# MCU099_01_MSPM0L1306_Target_Device.net
KiCad netlist of a schematic drawn in Altium Designer
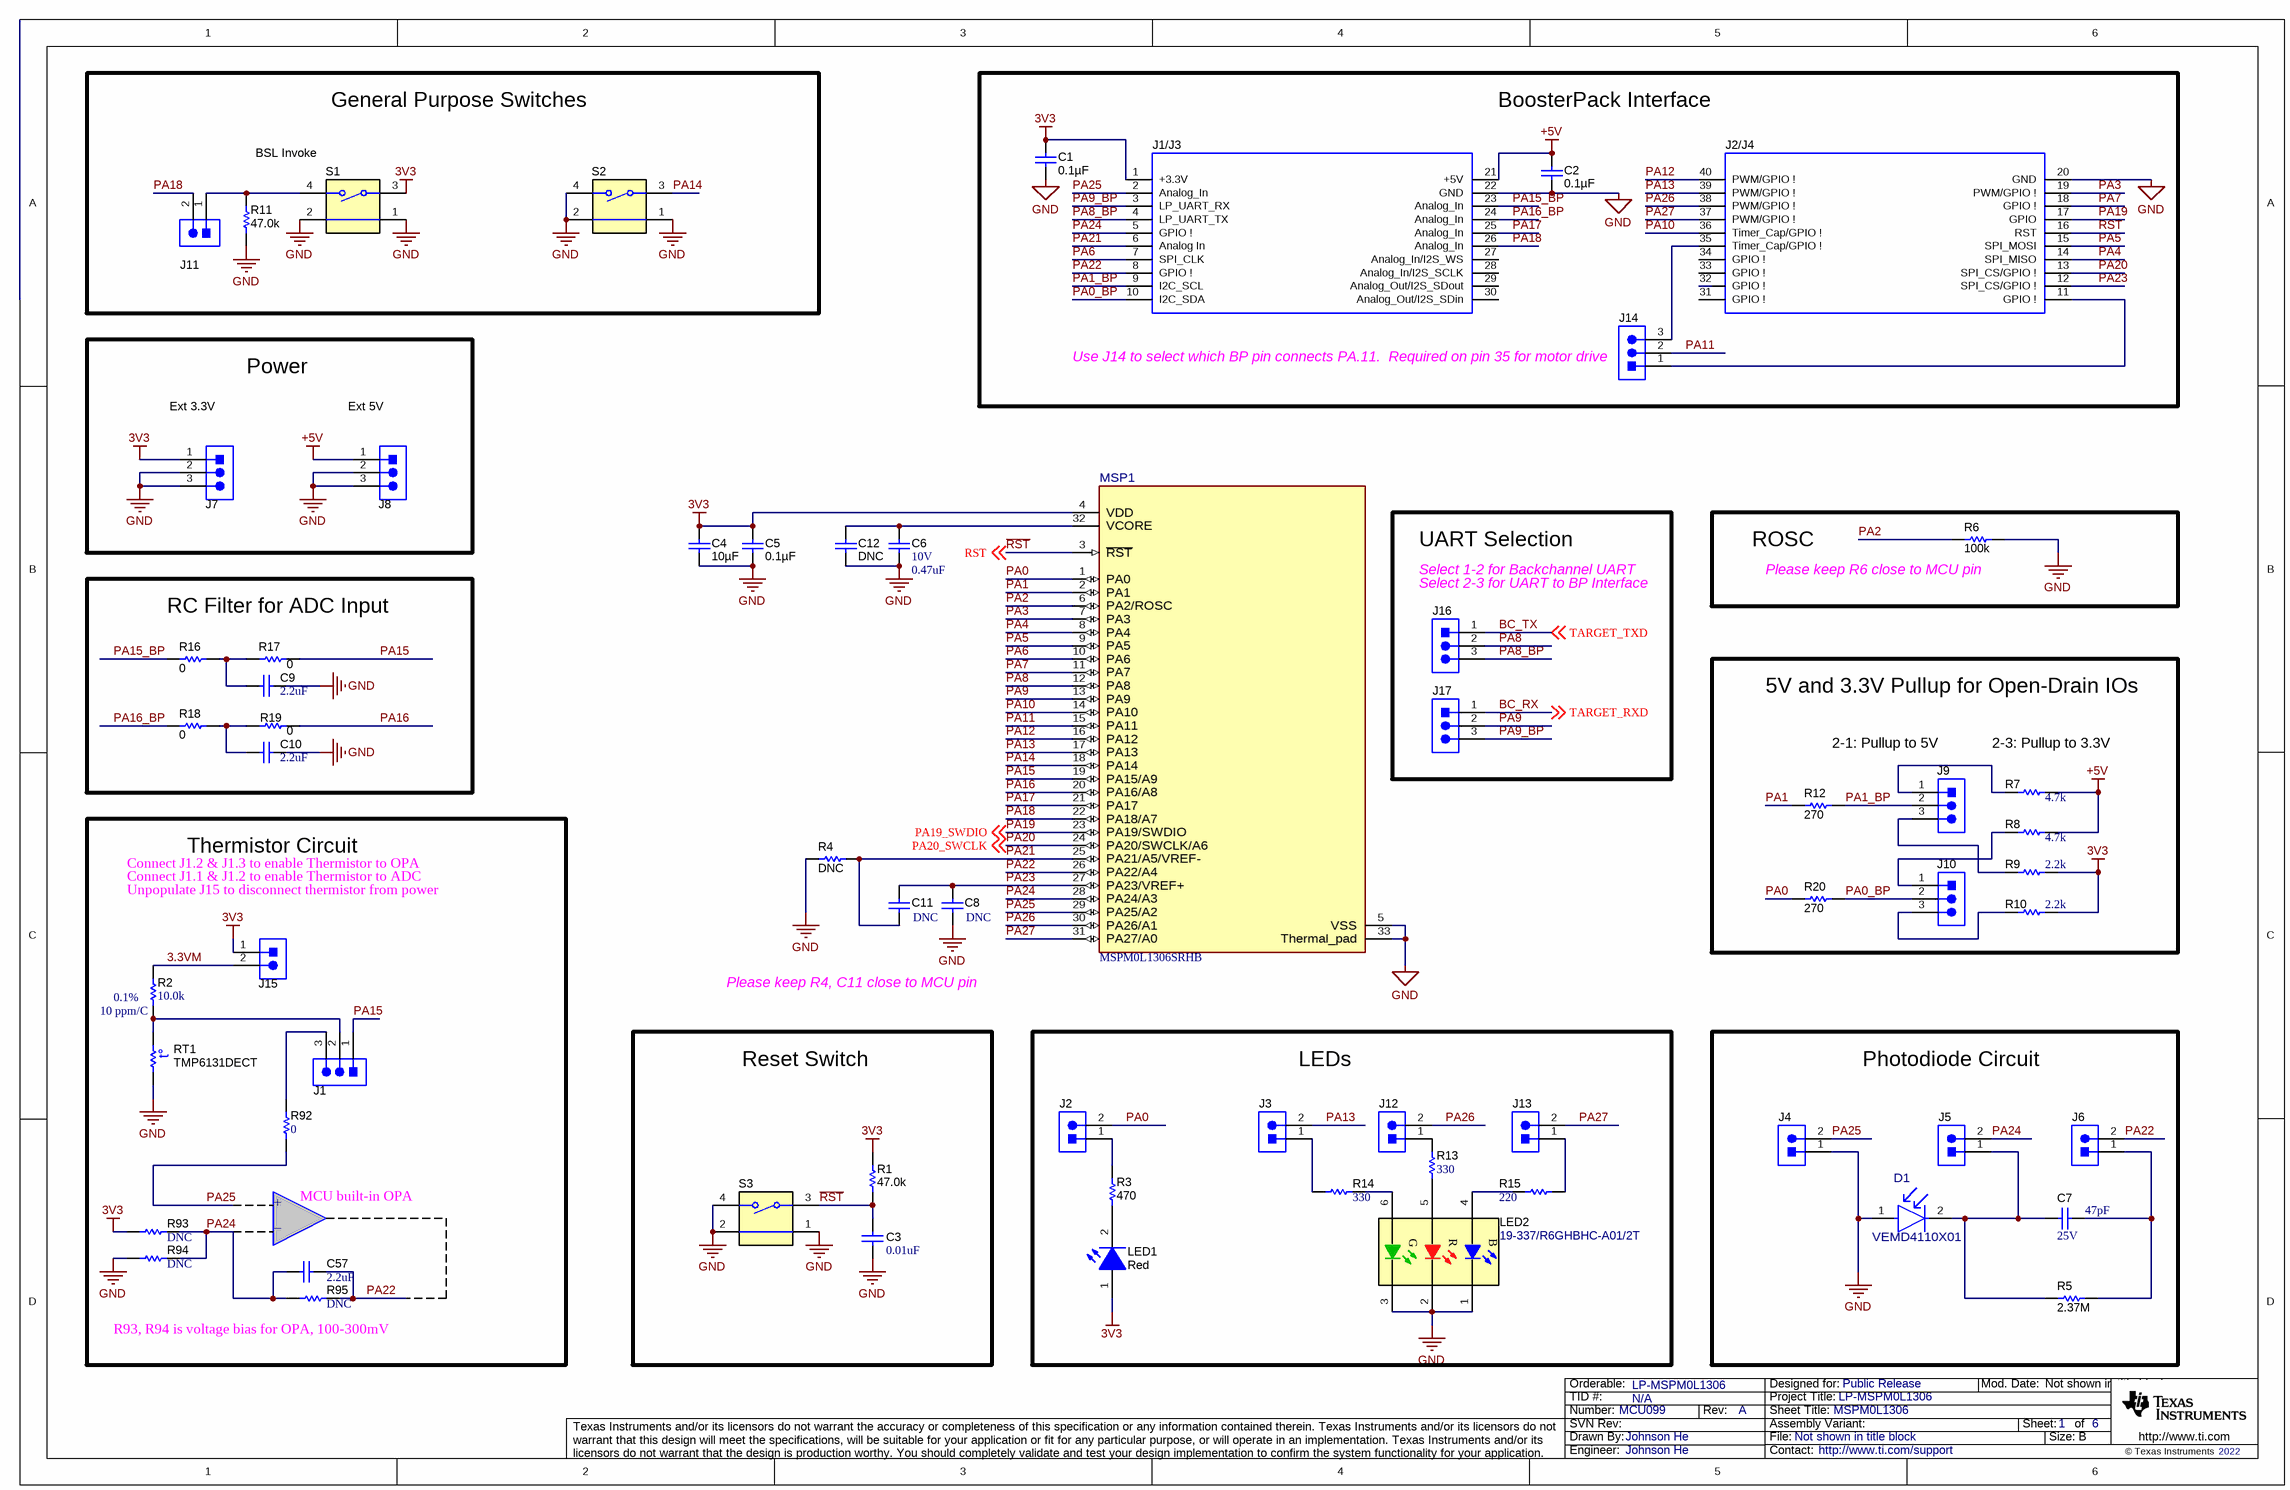
[diagram p0: MCU099_01_MSPM0L1306_Target_Device.SchDoc]

(export (version "E")
  (design (tool "Eeschema 10.0.6"))
  (components
    (comp (ref "C1")
      (value "CL10A104KA8NNNC")
      (footprint "0603")
      (description "CAP, CERM, 0.1 µF, 25 V,+/- 10%, X5R, 0603")
      (fields
        (field (name "VALUEDISPLAYED") "0.1µF")
        (field (name "MANUFACTURER") "Samsung Electro-Mechanics")
      )
      (libsource (lib "Altium Vault - TI") (part "Capacitor"))
    )
    (comp (ref "C2")
      (value "CL10A104KA8NNNC")
      (footprint "0603")
      (description "CAP, CERM, 0.1 µF, 25 V,+/- 10%, X5R, 0603")
      (fields
        (field (name "VALUEDISPLAYED") "0.1µF")
        (field (name "MANUFACTURER") "Samsung Electro-Mechanics")
      )
      (libsource (lib "Altium Vault - TI") (part "Capacitor"))
    )
    (comp (ref "C3")
      (value "885012205031")
      (footprint "0402")
      (description "CAP, CERM, 0.01 uF, 16 V, +/- 10%, X7R, 0402")
      (fields
        (field (name "MANUFACTURER") "Wurth Elektronik")
        (field (name "VALUEDISPLAYED") "0.01uF")
        (field (name "PUBLISHER") "Texas Instruments")
      )
      (libsource (lib "Altium Vault - TI") (part "Capacitor"))
    )
    (comp (ref "C4")
      (value "GRM188R61C106KAALD")
      (footprint "0603")
      (description "CAP, CERM, 10 µF, 16 V,+/- 10%, X5R, 0603")
      (fields (field (name "MANUFACTURER") "MuRata") (field (name "VALUEDISPLAYED") "10µF"))
      (libsource (lib "Altium Vault - TI") (part "Capacitor"))
    )
    (comp (ref "C5")
      (value "CL10A104KA8NNNC")
      (footprint "0603")
      (description "CAP, CERM, 0.1 µF, 25 V,+/- 10%, X5R, 0603")
      (fields
        (field (name "VALUEDISPLAYED") "0.1µF")
        (field (name "MANUFACTURER") "Samsung Electro-Mechanics")
      )
      (libsource (lib "Altium Vault - TI") (part "Capacitor"))
    )
    (comp (ref "C6")
      (value "C0603C474K8PACTU")
      (footprint "0603")
      (description "CAP, CERM, 0.47 uF, 10 V, +/- 10%, X5R, 0603")
      (fields
        (field (name "MANUFACTURER") "Kemet")
        (field (name "VDC_V") "10V")
        (field (name "VALUEDISPLAYED") "0.47uF")
        (field (name "PUBLISHER") "Texas Instruments")
      )
      (libsource (lib "Altium Vault - TI") (part "Capacitor"))
    )
    (comp (ref "C7")
      (value "GRM1555C1E470JA01D")
      (footprint "0402")
      (description "CAP, CERM, 47 pF, 25 V, +/- 5%, C0G/NP0, 0402")
      (fields
        (field (name "MANUFACTURER") "MuRata")
        (field (name "VDC_V") "25V")
        (field (name "VALUEDISPLAYED") "47pF")
        (field (name "PUBLISHER") "Texas Instruments")
      )
      (libsource (lib "Altium Vault - TI") (part "Capacitor"))
    )
    (comp (ref "C8")
      (value "C1608X5R1A105K080AC")
      (footprint "0603")
      (description "CAP, CERM, 1 uF, 10 V, +/- 10%, X5R, 0603")
      (fields
        (field (name "MANUFACTURER") "TDK")
        (field (name "VALUEDISPLAYED") "DNC")
        (field (name "PUBLISHER") "Texas Instruments")
      )
      (libsource (lib "Altium Vault - TI") (part "Capacitor"))
    )
    (comp (ref "C9")
      (value "C0603C225K8PACTU")
      (footprint "0603")
      (description "CAP, CERM, 2.2 uF, 10 V, +/- 10%, X5R, 0603")
      (fields
        (field (name "MANUFACTURER") "Kemet")
        (field (name "VALUEDISPLAYED") "2.2uF")
        (field (name "PUBLISHER") "Texas Instruments")
      )
      (libsource (lib "Altium Vault - TI") (part "Capacitor"))
    )
    (comp (ref "C10")
      (value "C0603C225K8PACTU")
      (footprint "0603")
      (description "CAP, CERM, 2.2 uF, 10 V, +/- 10%, X5R, 0603")
      (fields
        (field (name "MANUFACTURER") "Kemet")
        (field (name "VALUEDISPLAYED") "2.2uF")
        (field (name "PUBLISHER") "Texas Instruments")
      )
      (libsource (lib "Altium Vault - TI") (part "Capacitor"))
    )
    (comp (ref "C11")
      (value "C1608X5R1A105K080AC")
      (footprint "0603")
      (description "CAP, CERM, 1 uF, 10 V, +/- 10%, X5R, 0603")
      (fields
        (field (name "MANUFACTURER") "TDK")
        (field (name "VALUEDISPLAYED") "DNC")
        (field (name "PUBLISHER") "Texas Instruments")
      )
      (libsource (lib "Altium Vault - TI") (part "Capacitor"))
    )
    (comp (ref "C12")
      (value "CL10A104KA8NNNC")
      (footprint "0603")
      (description "CAP, CERM, 0.1 µF, 25 V,+/- 10%, X5R, 0603")
      (fields (field (name "VALUEDISPLAYED") "DNC") (field (name "MANUFACTURER") "Samsung Electro-Mechanics"))
      (libsource (lib "Altium Vault - TI") (part "Capacitor"))
    )
    (comp (ref "C57")
      (value "C0603C225K8PACTU")
      (footprint "0603")
      (description "CAP, CERM, 2.2 uF, 10 V, +/- 10%, X5R, 0603")
      (fields
        (field (name "MANUFACTURER") "Kemet")
        (field (name "VALUEDISPLAYED") "2.2uF")
        (field (name "PUBLISHER") "Texas Instruments")
      )
      (libsource (lib "Altium Vault - TI") (part "Capacitor"))
    )
    (comp (ref "D1")
      (value "VEMD4110X01")
      (footprint "FP-VEMD4110X01_0805-MFG")
      (description "Photodiode PIN Chip 910nm Automotive 2-Pin Case 0805(2012Metric) T/R")
      (fields
        (field (name "MANUFACTURER") "Vishay")
        (field (name "DIGIKEY PART NUMBER") "751-VEMD4110X01CT-ND")
      )
      (libsource (lib "Altium Vault - TI") (part "SYM-VEMD4110X01"))
    )
    (comp (ref "J1")
      (value "PEC03SAAN")
      (footprint "CONN_PEC03SAAN")
      (description "Header, 100mil, 3x1, Tin, TH")
      (fields
        (field (name "MANUFACTURER") "Sullins Connector Solutions")
        (field (name "PUBLISHER") "Texas Instruments")
      )
      (libsource (lib "Altium Vault - TI") (part "Header_3x1_Launchpad"))
    )
    (comp (ref "J1/J3")
      (value "SSQ-110-03-T-D")
      (footprint "BoosterPack_40pin_J1J3")
      (description "Receptacle, 2.54mm, 10x2, Tin, TH")
      (fields
        (field (name "MANUFACTURER") "Samtec")
        (field (name "ALTERNATE PARTNUMBER") "CRD-081413-A-G")
        (field (name "SYMBOLCREATOR") "a0412235")
        (field (name "PUBLISHER") "Texas Instruments")
      )
      (libsource (lib "Hardware") (part "BoosterPack_40pin_J1J3"))
    )
    (comp (ref "J2")
      (value "TSW-102-07-G-S")
      (footprint "TSW-102-07-G-S")
      (description "Header, 100mil, 2x1, Gold, TH")
      (fields (field (name "MANUFACTURER") "Samtec"))
      (libsource (lib "") (part "Header_2x1_1"))
    )
    (comp (ref "J2/J4")
      (value "SSQ-110-03-T-D")
      (footprint "BoosterPack_40pin_J2J4")
      (description "Receptacle, 2.54mm, 10x2, Tin, TH")
      (fields
        (field (name "MANUFACTURER") "Samtec")
        (field (name "ALTERNATE PARTNUMBER") "CRD-081413-A-G")
        (field (name "SYMBOLCREATOR") "a0412235")
        (field (name "PUBLISHER") "Texas Instruments")
      )
      (libsource (lib "Hardware") (part "BoosterPack_40pin_J2J4"))
    )
    (comp (ref "J3")
      (value "TSW-102-07-G-S")
      (footprint "TSW-102-07-G-S")
      (description "Header, 100mil, 2x1, Gold, TH")
      (fields (field (name "MANUFACTURER") "Samtec"))
      (libsource (lib "") (part "Header_2x1_1"))
    )
    (comp (ref "J4")
      (value "TSW-102-07-G-S")
      (footprint "TSW-102-07-G-S")
      (description "Header, 100mil, 2x1, Gold, TH")
      (fields (field (name "MANUFACTURER") "Samtec"))
      (libsource (lib "") (part "Header_2x1_1"))
    )
    (comp (ref "J5")
      (value "TSW-102-07-G-S")
      (footprint "TSW-102-07-G-S")
      (description "Header, 100mil, 2x1, Gold, TH")
      (fields (field (name "MANUFACTURER") "Samtec"))
      (libsource (lib "") (part "Header_2x1_1"))
    )
    (comp (ref "J6")
      (value "TSW-102-07-G-S")
      (footprint "TSW-102-07-G-S")
      (description "Header, 100mil, 2x1, Gold, TH")
      (fields (field (name "MANUFACTURER") "Samtec"))
      (libsource (lib "") (part "Header_2x1_1"))
    )
    (comp (ref "J7")
      (value "PEC03SAAN")
      (footprint "PEC03SAAN_Launchpad_3V3")
      (description "Header, 100mil, 3x1, Tin, TH")
      (fields
        (field (name "MANUFACTURER") "Sullins Connector Solutions")
        (field (name "PUBLISHER") "Texas Instruments")
      )
      (libsource (lib "") (part "Header_3x1_Launchpad_1"))
    )
    (comp (ref "J8")
      (value "PEC03SAAN")
      (footprint "PEC03SAAN_Launchpad_5V0")
      (description "Header, 100mil, 3x1, Tin, TH")
      (fields
        (field (name "MANUFACTURER") "Sullins Connector Solutions")
        (field (name "PUBLISHER") "Texas Instruments")
      )
      (libsource (lib "") (part "Header_3x1_Launchpad_1"))
    )
    (comp (ref "J9")
      (value "PEC03SAAN")
      (footprint "CONN_PEC03SAAN")
      (description "Header, 100mil, 3x1, Tin, TH")
      (fields
        (field (name "MANUFACTURER") "Sullins Connector Solutions")
        (field (name "PUBLISHER") "Texas Instruments")
      )
      (libsource (lib "") (part "Header_3x1_Launchpad_1"))
    )
    (comp (ref "J10")
      (value "PEC03SAAN")
      (footprint "CONN_PEC03SAAN")
      (description "Header, 100mil, 3x1, Tin, TH")
      (fields
        (field (name "MANUFACTURER") "Sullins Connector Solutions")
        (field (name "PUBLISHER") "Texas Instruments")
      )
      (libsource (lib "") (part "Header_3x1_Launchpad_1"))
    )
    (comp (ref "J11")
      (value "TSW-102-07-G-S")
      (footprint "TSW-102-07-G-S")
      (description "Header, 100mil, 2x1, Gold, TH")
      (fields (field (name "MANUFACTURER") "Samtec"))
      (libsource (lib "Altium Vault - TI") (part "Header_2x1"))
    )
    (comp (ref "J12")
      (value "TSW-102-07-G-S")
      (footprint "TSW-102-07-G-S")
      (description "Header, 100mil, 2x1, Gold, TH")
      (fields (field (name "MANUFACTURER") "Samtec"))
      (libsource (lib "") (part "Header_2x1_1"))
    )
    (comp (ref "J13")
      (value "TSW-102-07-G-S")
      (footprint "TSW-102-07-G-S")
      (description "Header, 100mil, 2x1, Gold, TH")
      (fields (field (name "MANUFACTURER") "Samtec"))
      (libsource (lib "") (part "Header_2x1_1"))
    )
    (comp (ref "J14")
      (value "PEC03SAAN")
      (footprint "CONN_PEC03SAAN")
      (description "Header, 100mil, 3x1, Tin, TH")
      (fields
        (field (name "MANUFACTURER") "Sullins Connector Solutions")
        (field (name "PUBLISHER") "Texas Instruments")
      )
      (libsource (lib "") (part "Header_3x1_Launchpad_2"))
    )
    (comp (ref "J15")
      (value "90120-0122")
      (footprint "CONN_90120-0122")
      (description "Header, 100mil, 2x1, Tin, TH")
      (fields (field (name "MANUFACTURER") "Molex") (field (name "PUBLISHER") "Texas Instruments"))
      (libsource (lib "") (part "Header_2x1_2"))
    )
    (comp (ref "J16")
      (value "PEC03SAAN")
      (footprint "CONN_PEC03SAAN")
      (description "Header, 100mil, 3x1, Tin, TH")
      (fields
        (field (name "MANUFACTURER") "Sullins Connector Solutions")
        (field (name "PUBLISHER") "Texas Instruments")
      )
      (libsource (lib "Altium Vault - TI") (part "Header_3x1_Launchpad"))
    )
    (comp (ref "J17")
      (value "PEC03SAAN")
      (footprint "CONN_PEC03SAAN")
      (description "Header, 100mil, 3x1, Tin, TH")
      (fields
        (field (name "MANUFACTURER") "Sullins Connector Solutions")
        (field (name "PUBLISHER") "Texas Instruments")
      )
      (libsource (lib "Altium Vault - TI") (part "Header_3x1_Launchpad"))
    )
    (comp (ref "LED1")
      (value "Red")
      (footprint "1111C_Red")
      (description "LED, Red, SMD")
      (fields
        (field (name "MANUFACTURER") "Stanley Electric Co., LTD")
        (field (name "PARTNUMBER") "BR1111C-TR")
      )
      (libsource (lib "Altium Vault - TI") (part "LED"))
    )
    (comp (ref "LED2")
      (value "19-337/R6GHBHC-A01/2T")
      (footprint "19-337_RGB")
      (description "LED, RGB, TH")
      (fields (field (name "MANUFACTURER") "Everlight"))
      (libsource (lib "Altium Vault - TI") (part "LED_RGB_A456K123"))
    )
    (comp (ref "MSP1")
      (value "MSPM0L1306SRHB")
      (footprint "RHB0032N-MFG")
      (description "MSPM0L130x Mixed-Signal Microcontrollers")
      (fields (field (name "MANUFACTURER") "Texas Instruments") (field (name "PARTNUMBER") "MSPM0L1306SRHB"))
      (libsource (lib "Altium Vault - TI") (part "SYM-MSPM0L1306SRHB"))
    )
    (comp (ref "R1")
      (value "RC0402FR-0747KL")
      (footprint "0402")
      (description "RES, 47.0 k, 1%, 0.0625 W, 0402")
      (fields
        (field (name "MANUFACTURER") "Yageo America")
        (field (name "VALUEDISPLAYED") "47.0k")
        (field (name "PUBLISHER") "Texas Instruments")
      )
      (libsource (lib "Altium Vault - TI") (part "Resistor"))
    )
    (comp (ref "R2")
      (value "ERA3ARB103V")
      (footprint "ERA3A")
      (description "RES, 10.0 k, 0.1%, 0.1 W, AEC-Q200 Grade 0, 1.6x0.8mm")
      (fields
        (field (name "TOLERANCE_%") "0.1%")
        (field (name "MANUFACTURER") "Panasonic")
        (field (name "TEMPCO") "10 ppm/C")
        (field (name "VALUEDISPLAYED") "10.0k")
      )
      (libsource (lib "Altium Vault - TI") (part "Resistor"))
    )
    (comp (ref "R3")
      (value "RC0402FR-07470RL")
      (footprint "0402")
      (description "RES, 470, 1%, 0.063 W, 0402")
      (fields
        (field (name "MANUFACTURER") "Yageo America")
        (field (name "VALUEDISPLAYED") "470")
        (field (name "PUBLISHER") "Texas Instruments")
      )
      (libsource (lib "Altium Vault - TI") (part "Resistor"))
    )
    (comp (ref "R4")
      (value "MCT06030Z0000ZP500")
      (footprint "0603")
      (description "RES, 0, 5%, 0.125 W, 0603")
      (fields
        (field (name "MANUFACTURER") "Vishay/Beyschlag")
        (field (name "VALUEDISPLAYED") "DNC")
        (field (name "PUBLISHER") "Texas Instruments")
      )
      (libsource (lib "Altium Vault - TI") (part "Resistor"))
    )
    (comp (ref "R5")
      (value "CRCW06032M37FKEA")
      (footprint "0603")
      (description "RES, 2.37 M, 1%, 0.1 W, AEC-Q200 Grade 0, 0603")
      (fields (field (name "MANUFACTURER") "Vishay-Dale") (field (name "VALUEDISPLAYED") "2.37M"))
      (libsource (lib "Altium Vault - TI") (part "Resistor"))
    )
    (comp (ref "R6")
      (value "RG1005P-104-B-T5")
      (footprint "0402")
      (description "RES, 100 k, 0.1%, 0.063 W, 0402")
      (fields
        (field (name "MANUFACTURER") "Susumu Co Ltd")
        (field (name "VALUEDISPLAYED") "100k")
        (field (name "PUBLISHER") "Texas Instruments")
      )
      (libsource (lib "Altium Vault - TI") (part "Resistor"))
    )
    (comp (ref "R7")
      (value "RC0603JR-074K7L")
      (footprint "0603")
      (description "RES, 4.7 k, 5%, 0.1 W, 0603")
      (fields (field (name "MANUFACTURER") "Yageo") (field (name "VALUEDISPLAYED") "4.7k"))
      (libsource (lib "Altium Vault - TI") (part "Resistor"))
    )
    (comp (ref "R8")
      (value "RC0603JR-074K7L")
      (footprint "0603")
      (description "RES, 4.7 k, 5%, 0.1 W, 0603")
      (fields (field (name "MANUFACTURER") "Yageo") (field (name "VALUEDISPLAYED") "4.7k"))
      (libsource (lib "Altium Vault - TI") (part "Resistor"))
    )
    (comp (ref "R9")
      (value "RC0603JR-0710KL")
      (footprint "0603")
      (description "RES, 2.2 k, 5%, 0.1 W, 0603")
      (fields
        (field (name "PARTNUMBER") "RC0603JR-072K2L")
        (field (name "MANUFACTURER") "Yageo")
        (field (name "VALUEDISPLAYED") "2.2k")
      )
      (libsource (lib "Altium Vault - TI") (part "Resistor"))
    )
    (comp (ref "R10")
      (value "RC0603JR-0710KL")
      (footprint "0603")
      (description "RES, 2.2 k, 5%, 0.1 W, 0603")
      (fields
        (field (name "PARTNUMBER") "RC0603JR-072K2L")
        (field (name "MANUFACTURER") "Yageo")
        (field (name "VALUEDISPLAYED") "2.2k")
      )
      (libsource (lib "Altium Vault - TI") (part "Resistor"))
    )
    (comp (ref "R11")
      (value "RC0402FR-0747KL")
      (footprint "0402")
      (description "RES, 47.0 k, 1%, 0.0625 W, 0402")
      (fields
        (field (name "MANUFACTURER") "Yageo America")
        (field (name "VALUEDISPLAYED") "47.0k")
        (field (name "PUBLISHER") "Texas Instruments")
      )
      (libsource (lib "Altium Vault - TI") (part "Resistor"))
    )
    (comp (ref "R12")
      (value "RC0603JR-07270RL")
      (footprint "0603")
      (description "RES, 270, 5%, 0.1 W, 0603")
      (fields (field (name "MANUFACTURER") "Yageo") (field (name "VALUEDISPLAYED") "270"))
      (libsource (lib "Altium Vault - TI") (part "Resistor"))
    )
    (comp (ref "R13")
      (value "CRCW0402330RJNED")
      (footprint "0402")
      (description "RES, 330, 5%, 0.063 W, 0402")
      (fields
        (field (name "MANUFACTURER") "Vishay-Dale")
        (field (name "VALUEDISPLAYED") "330")
        (field (name "PUBLISHER") "Texas Instruments")
      )
      (libsource (lib "Altium Vault - TI") (part "Resistor"))
    )
    (comp (ref "R14")
      (value "CRCW0402330RJNED")
      (footprint "0402")
      (description "RES, 330, 5%, 0.063 W, 0402")
      (fields
        (field (name "MANUFACTURER") "Vishay-Dale")
        (field (name "VALUEDISPLAYED") "330")
        (field (name "PUBLISHER") "Texas Instruments")
      )
      (libsource (lib "Altium Vault - TI") (part "Resistor"))
    )
    (comp (ref "R15")
      (value "CRCW0402220RJNED")
      (footprint "0402")
      (description "RES, 220, 5%, 0.063 W, 0402")
      (fields
        (field (name "MANUFACTURER") "Vishay-Dale")
        (field (name "VALUEDISPLAYED") "220")
        (field (name "PUBLISHER") "Texas Instruments")
      )
      (libsource (lib "Altium Vault - TI") (part "Resistor"))
    )
    (comp (ref "R16")
      (value "MCT06030Z0000ZP500")
      (footprint "0603")
      (description "RES, 0, 5%, 0.125 W, 0603")
      (fields
        (field (name "MANUFACTURER") "Vishay/Beyschlag")
        (field (name "VALUEDISPLAYED") "0")
        (field (name "PUBLISHER") "Texas Instruments")
      )
      (libsource (lib "Altium Vault - TI") (part "Resistor"))
    )
    (comp (ref "R17")
      (value "MCT06030Z0000ZP500")
      (footprint "0603")
      (description "RES, 0, 5%, 0.125 W, 0603")
      (fields
        (field (name "MANUFACTURER") "Vishay/Beyschlag")
        (field (name "VALUEDISPLAYED") "0")
        (field (name "PUBLISHER") "Texas Instruments")
      )
      (libsource (lib "Altium Vault - TI") (part "Resistor"))
    )
    (comp (ref "R18")
      (value "MCT06030Z0000ZP500")
      (footprint "0603")
      (description "RES, 0, 5%, 0.125 W, 0603")
      (fields
        (field (name "MANUFACTURER") "Vishay/Beyschlag")
        (field (name "VALUEDISPLAYED") "0")
        (field (name "PUBLISHER") "Texas Instruments")
      )
      (libsource (lib "Altium Vault - TI") (part "Resistor"))
    )
    (comp (ref "R19")
      (value "MCT06030Z0000ZP500")
      (footprint "0603")
      (description "RES, 0, 5%, 0.125 W, 0603")
      (fields
        (field (name "MANUFACTURER") "Vishay/Beyschlag")
        (field (name "VALUEDISPLAYED") "0")
        (field (name "PUBLISHER") "Texas Instruments")
      )
      (libsource (lib "Altium Vault - TI") (part "Resistor"))
    )
    (comp (ref "R20")
      (value "RC0603JR-07270RL")
      (footprint "0603")
      (description "RES, 270, 5%, 0.1 W, 0603")
      (fields (field (name "MANUFACTURER") "Yageo") (field (name "VALUEDISPLAYED") "270"))
      (libsource (lib "Altium Vault - TI") (part "Resistor"))
    )
    (comp (ref "R92")
      (value "RC0603JR-070RL")
      (footprint "0603")
      (description "RES, 0, 5%, 0.1 W, 0603")
      (fields (field (name "MANUFACTURER") "Yageo") (field (name "VALUEDISPLAYED") "0"))
      (libsource (lib "Altium Vault - TI") (part "Resistor"))
    )
    (comp (ref "R93")
      (value "RC0603JR-070RL")
      (footprint "0603")
      (description "RES, 0, 5%, 0.1 W, 0603")
      (fields (field (name "MANUFACTURER") "Yageo") (field (name "VALUEDISPLAYED") "DNC"))
      (libsource (lib "Altium Vault - TI") (part "Resistor"))
    )
    (comp (ref "R94")
      (value "RC0603JR-070RL")
      (footprint "0603")
      (description "RES, 0, 5%, 0.1 W, 0603")
      (fields (field (name "MANUFACTURER") "Yageo") (field (name "VALUEDISPLAYED") "DNC"))
      (libsource (lib "Altium Vault - TI") (part "Resistor"))
    )
    (comp (ref "R95")
      (value "RC0603JR-070RL")
      (footprint "0603")
      (description "RES, 0, 5%, 0.1 W, 0603")
      (fields (field (name "MANUFACTURER") "Yageo") (field (name "VALUEDISPLAYED") "DNC"))
      (libsource (lib "Altium Vault - TI") (part "Resistor"))
    )
    (comp (ref "RT1")
      (value "TMP6131DECT")
      (footprint "DEC0002A")
      (description "Thermistor, DEC0002A (X1SON-2)")
      (fields
        (field (name "ALTERNATE PARTNUMBER") "TMP6131DECR")
        (field (name "PARTNUMBER") "TMP6131DECT")
        (field (name "MANUFACTURER") "Texas Instruments")
      )
      (libsource (lib "Altium Vault - TI") (part "Thermistor"))
    )
    (comp (ref "S1")
      (value "1188E-1K2-V-TR")
      (footprint "SW_1188E")
      (description "Switch, SPST, 0.05 A, 12 VDC, SMD")
      (fields (field (name "MANUFACTURER") "Diptronics") (field (name "PUBLISHER") "Texas Instruments"))
      (libsource (lib "Altium Vault - TI") (part "SW_1188E"))
    )
    (comp (ref "S2")
      (value "1188E-1K2-V-TR")
      (footprint "SW_1188E")
      (description "Switch, SPST, 0.05 A, 12 VDC, SMD")
      (fields (field (name "MANUFACTURER") "Diptronics") (field (name "PUBLISHER") "Texas Instruments"))
      (libsource (lib "Altium Vault - TI") (part "SW_1188E"))
    )
    (comp (ref "S3")
      (value "1188E-1K2-V-TR")
      (footprint "SW_1188E")
      (description "Switch, SPST, 0.05 A, 12 VDC, SMD")
      (fields (field (name "MANUFACTURER") "Diptronics") (field (name "PUBLISHER") "Texas Instruments"))
      (libsource (lib "Altium Vault - TI") (part "SW_1188E"))
    )
  )
  (nets
    (net (code "1") (name "+5V") (class "Default")
      (node (ref "C2") (pin "1") (pinfunction "1_1") (pintype "passive"))
      (node (ref "J1/J3") (pin "21") (pinfunction "+5V_21") (pintype "power_in"))
      (node (ref "J8") (pin "1") (pinfunction "1_1") (pintype "passive"))
      (node (ref "R7") (pin "2") (pinfunction "2_2") (pintype "passive"))
      (node (ref "R8") (pin "2") (pinfunction "2_2") (pintype "passive"))
    )
    (net (code "2") (name "/3.3VM") (class "Default")
      (node (ref "J15") (pin "2") (pinfunction "2_2") (pintype "passive"))
      (node (ref "R2") (pin "2") (pinfunction "2_2") (pintype "passive"))
    )
    (net (code "3") (name "/PA0") (class "Default")
      (node (ref "J2") (pin "2") (pinfunction "2_2") (pintype "passive"))
      (node (ref "MSP1") (pin "1") (pinfunction "PA0_1") (pintype "bidirectional"))
      (node (ref "R20") (pin "1") (pinfunction "1_1") (pintype "passive"))
    )
    (net (code "4") (name "/PA0_BP") (class "Default")
      (node (ref "J1/J3") (pin "10") (pinfunction "I2C_SDA_10") (pintype "passive"))
      (node (ref "J10") (pin "2") (pinfunction "2_2") (pintype "passive"))
      (node (ref "R20") (pin "2") (pinfunction "2_2") (pintype "passive"))
    )
    (net (code "5") (name "/PA1") (class "Default")
      (node (ref "MSP1") (pin "2") (pinfunction "PA1_2") (pintype "bidirectional"))
      (node (ref "R12") (pin "1") (pinfunction "1_1") (pintype "passive"))
    )
    (net (code "6") (name "/PA1_BP") (class "Default")
      (node (ref "J1/J3") (pin "9") (pinfunction "I2C_SCL_9") (pintype "passive"))
      (node (ref "J9") (pin "2") (pinfunction "2_2") (pintype "passive"))
      (node (ref "R12") (pin "2") (pinfunction "2_2") (pintype "passive"))
    )
    (net (code "7") (name "/PA2") (class "Default")
      (node (ref "MSP1") (pin "6") (pinfunction "PA2/ROSC_6") (pintype "bidirectional"))
      (node (ref "R6") (pin "1") (pinfunction "1_1") (pintype "passive"))
    )
    (net (code "8") (name "/PA3") (class "Default")
      (node (ref "J2/J4") (pin "19") (pinfunction "PWM/GPIO_!_19") (pintype "passive"))
      (node (ref "MSP1") (pin "7") (pinfunction "PA3_7") (pintype "bidirectional"))
    )
    (net (code "9") (name "/PA4") (class "Default")
      (node (ref "J2/J4") (pin "14") (pinfunction "SPI_MISO_14") (pintype "passive"))
      (node (ref "MSP1") (pin "8") (pinfunction "PA4_8") (pintype "bidirectional"))
    )
    (net (code "10") (name "/PA5") (class "Default")
      (node (ref "J2/J4") (pin "15") (pinfunction "SPI_MOSI_15") (pintype "passive"))
      (node (ref "MSP1") (pin "9") (pinfunction "PA5_9") (pintype "bidirectional"))
    )
    (net (code "11") (name "/PA6") (class "Default")
      (node (ref "J1/J3") (pin "7") (pinfunction "SPI_CLK_7") (pintype "passive"))
      (node (ref "MSP1") (pin "10") (pinfunction "PA6_10") (pintype "bidirectional"))
    )
    (net (code "12") (name "/PA7") (class "Default")
      (node (ref "J2/J4") (pin "18") (pinfunction "GPIO_!_18") (pintype "passive"))
      (node (ref "MSP1") (pin "11") (pinfunction "PA7_11") (pintype "bidirectional"))
    )
    (net (code "13") (name "/PA8") (class "Default")
      (node (ref "J16") (pin "2") (pinfunction "2_2") (pintype "passive"))
      (node (ref "MSP1") (pin "12") (pinfunction "PA8_12") (pintype "bidirectional"))
    )
    (net (code "14") (name "/PA8_BP") (class "Default")
      (node (ref "J1/J3") (pin "4") (pinfunction "LP_UART_TX_4") (pintype "passive"))
      (node (ref "J16") (pin "3") (pinfunction "3_3") (pintype "passive"))
    )
    (net (code "15") (name "/PA9") (class "Default")
      (node (ref "J17") (pin "2") (pinfunction "2_2") (pintype "passive"))
      (node (ref "MSP1") (pin "13") (pinfunction "PA9_13") (pintype "bidirectional"))
    )
    (net (code "16") (name "/PA9_BP") (class "Default")
      (node (ref "J1/J3") (pin "3") (pinfunction "LP_UART_RX_3") (pintype "passive"))
      (node (ref "J17") (pin "3") (pinfunction "3_3") (pintype "passive"))
    )
    (net (code "17") (name "/PA10") (class "Default")
      (node (ref "J2/J4") (pin "36") (pinfunction "Timer_Cap/GPIO_!_36") (pintype "passive"))
      (node (ref "MSP1") (pin "14") (pinfunction "PA10_14") (pintype "bidirectional"))
    )
    (net (code "18") (name "/PA11") (class "Default")
      (node (ref "J14") (pin "2") (pinfunction "2_2") (pintype "passive"))
      (node (ref "MSP1") (pin "15") (pinfunction "PA11_15") (pintype "bidirectional"))
    )
    (net (code "19") (name "/PA12") (class "Default")
      (node (ref "J2/J4") (pin "40") (pinfunction "PWM/GPIO_!_40") (pintype "passive"))
      (node (ref "MSP1") (pin "16") (pinfunction "PA12_16") (pintype "bidirectional"))
    )
    (net (code "20") (name "/PA13") (class "Default")
      (node (ref "J2/J4") (pin "39") (pinfunction "PWM/GPIO_!_39") (pintype "passive"))
      (node (ref "J3") (pin "2") (pinfunction "2_2") (pintype "passive"))
      (node (ref "MSP1") (pin "17") (pinfunction "PA13_17") (pintype "bidirectional"))
    )
    (net (code "21") (name "/PA14") (class "Default")
      (node (ref "MSP1") (pin "18") (pinfunction "PA14_18") (pintype "bidirectional"))
      (node (ref "S2") (pin "3") (pinfunction "3_3") (pintype "passive"))
    )
    (net (code "22") (name "/PA15") (class "Default")
      (node (ref "J1") (pin "1") (pinfunction "1_1") (pintype "passive"))
      (node (ref "MSP1") (pin "19") (pinfunction "PA15/A9_19") (pintype "bidirectional"))
      (node (ref "R17") (pin "2") (pinfunction "2_2") (pintype "passive"))
    )
    (net (code "23") (name "/PA15_BP") (class "Default")
      (node (ref "J1/J3") (pin "23") (pinfunction "Analog_In_23") (pintype "passive"))
      (node (ref "R16") (pin "1") (pinfunction "1_1") (pintype "passive"))
    )
    (net (code "24") (name "/PA16") (class "Default")
      (node (ref "MSP1") (pin "20") (pinfunction "PA16/A8_20") (pintype "bidirectional"))
      (node (ref "R19") (pin "2") (pinfunction "2_2") (pintype "passive"))
    )
    (net (code "25") (name "/PA16_BP") (class "Default")
      (node (ref "J1/J3") (pin "24") (pinfunction "Analog_In_24") (pintype "passive"))
      (node (ref "R18") (pin "1") (pinfunction "1_1") (pintype "passive"))
    )
    (net (code "26") (name "/PA17") (class "Default")
      (node (ref "J1/J3") (pin "25") (pinfunction "Analog_In_25") (pintype "passive"))
      (node (ref "MSP1") (pin "21") (pinfunction "PA17_21") (pintype "bidirectional"))
    )
    (net (code "27") (name "/PA18") (class "Default")
      (node (ref "J1/J3") (pin "26") (pinfunction "Analog_In_26") (pintype "passive"))
      (node (ref "J11") (pin "2") (pinfunction "2_2") (pintype "passive"))
      (node (ref "MSP1") (pin "22") (pinfunction "PA18/A7_22") (pintype "bidirectional"))
    )
    (net (code "28") (name "/PA21") (class "Default")
      (node (ref "C11") (pin "2") (pinfunction "2_2") (pintype "passive"))
      (node (ref "J1/J3") (pin "6") (pinfunction "Analog_In_6") (pintype "passive"))
      (node (ref "MSP1") (pin "25") (pinfunction "PA21/A5/VREF-_25") (pintype "bidirectional"))
      (node (ref "R4") (pin "2") (pinfunction "2_2") (pintype "passive"))
    )
    (net (code "29") (name "/PA22") (class "Default")
      (node (ref "C57") (pin "2") (pinfunction "2_2") (pintype "passive"))
      (node (ref "J1/J3") (pin "8") (pinfunction "GPIO_!_8") (pintype "passive"))
      (node (ref "J6") (pin "2") (pinfunction "2_2") (pintype "passive"))
      (node (ref "MSP1") (pin "26") (pinfunction "PA22/A4_26") (pintype "bidirectional"))
      (node (ref "R95") (pin "2") (pinfunction "2_2") (pintype "passive"))
    )
    (net (code "30") (name "/PA23") (class "Default")
      (node (ref "C11") (pin "1") (pinfunction "1_1") (pintype "passive"))
      (node (ref "C8") (pin "1") (pinfunction "1_1") (pintype "passive"))
      (node (ref "J2/J4") (pin "12") (pinfunction "SPI_CS/GPIO_!_12") (pintype "passive"))
      (node (ref "MSP1") (pin "27") (pinfunction "PA23/VREF+_27") (pintype "bidirectional"))
    )
    (net (code "31") (name "/PA24") (class "Default")
      (node (ref "C57") (pin "1") (pinfunction "1_1") (pintype "passive"))
      (node (ref "J1/J3") (pin "5") (pinfunction "GPIO_!_5") (pintype "passive"))
      (node (ref "J5") (pin "2") (pinfunction "2_2") (pintype "passive"))
      (node (ref "MSP1") (pin "28") (pinfunction "PA24/A3_28") (pintype "bidirectional"))
      (node (ref "R93") (pin "2") (pinfunction "2_2") (pintype "passive"))
      (node (ref "R94") (pin "2") (pinfunction "2_2") (pintype "passive"))
      (node (ref "R95") (pin "1") (pinfunction "1_1") (pintype "passive"))
    )
    (net (code "32") (name "/PA25") (class "Default")
      (node (ref "J1/J3") (pin "2") (pinfunction "Analog_In_2") (pintype "passive"))
      (node (ref "J4") (pin "2") (pinfunction "2_2") (pintype "passive"))
      (node (ref "MSP1") (pin "29") (pinfunction "PA25/A2_29") (pintype "bidirectional"))
      (node (ref "R92") (pin "1") (pinfunction "1_1") (pintype "passive"))
    )
    (net (code "33") (name "/PA26") (class "Default")
      (node (ref "J12") (pin "2") (pinfunction "2_2") (pintype "passive"))
      (node (ref "J2/J4") (pin "38") (pinfunction "PWM/GPIO_!_38") (pintype "passive"))
      (node (ref "MSP1") (pin "30") (pinfunction "PA26/A1_30") (pintype "bidirectional"))
    )
    (net (code "34") (name "/PA27") (class "Default")
      (node (ref "J13") (pin "2") (pinfunction "2_2") (pintype "passive"))
      (node (ref "J2/J4") (pin "37") (pinfunction "PWM/GPIO_!_37") (pintype "passive"))
      (node (ref "MSP1") (pin "31") (pinfunction "PA27/A0_31") (pintype "bidirectional"))
    )
    (net (code "35") (name "3V3") (class "Default")
      (node (ref "C1") (pin "1") (pinfunction "1_1") (pintype "passive"))
      (node (ref "C4") (pin "1") (pinfunction "1_1") (pintype "passive"))
      (node (ref "C5") (pin "1") (pinfunction "1_1") (pintype "passive"))
      (node (ref "J1/J3") (pin "1") (pinfunction "+3.3V_1") (pintype "power_in"))
      (node (ref "J15") (pin "1") (pinfunction "1_1") (pintype "passive"))
      (node (ref "J7") (pin "1") (pinfunction "1_1") (pintype "passive"))
      (node (ref "LED1") (pin "1") (pinfunction "A_1") (pintype "passive"))
      (node (ref "MSP1") (pin "4") (pinfunction "VDD_4") (pintype "power_in"))
      (node (ref "R1") (pin "2") (pinfunction "2_2") (pintype "passive"))
      (node (ref "R10") (pin "2") (pinfunction "2_2") (pintype "passive"))
      (node (ref "R9") (pin "2") (pinfunction "2_2") (pintype "passive"))
      (node (ref "R93") (pin "1") (pinfunction "1_1") (pintype "passive"))
      (node (ref "S1") (pin "3") (pinfunction "3_3") (pintype "passive"))
    )
    (net (code "36") (name "GND") (class "Default")
      (node (ref "C1") (pin "2") (pinfunction "2_2") (pintype "passive"))
      (node (ref "C10") (pin "2") (pinfunction "2_2") (pintype "passive"))
      (node (ref "C12") (pin "2") (pinfunction "2_2") (pintype "passive"))
      (node (ref "C2") (pin "2") (pinfunction "2_2") (pintype "passive"))
      (node (ref "C3") (pin "2") (pinfunction "2_2") (pintype "passive"))
      (node (ref "C4") (pin "2") (pinfunction "2_2") (pintype "passive"))
      (node (ref "C5") (pin "2") (pinfunction "2_2") (pintype "passive"))
      (node (ref "C6") (pin "2") (pinfunction "2_2") (pintype "passive"))
      (node (ref "C8") (pin "2") (pinfunction "2_2") (pintype "passive"))
      (node (ref "C9") (pin "2") (pinfunction "2_2") (pintype "passive"))
      (node (ref "D1") (pin "1") (pinfunction "ANODE_1") (pintype "passive"))
      (node (ref "J1/J3") (pin "22") (pinfunction "GND_22") (pintype "power_in"))
      (node (ref "J2/J4") (pin "20") (pinfunction "GND_20") (pintype "power_in"))
      (node (ref "J4") (pin "1") (pinfunction "1_1") (pintype "passive"))
      (node (ref "J7") (pin "2") (pinfunction "2_2") (pintype "passive"))
      (node (ref "J7") (pin "3") (pinfunction "3_3") (pintype "passive"))
      (node (ref "J8") (pin "2") (pinfunction "2_2") (pintype "passive"))
      (node (ref "J8") (pin "3") (pinfunction "3_3") (pintype "passive"))
      (node (ref "LED2") (pin "1") (pinfunction "K_1") (pintype "passive"))
      (node (ref "LED2") (pin "2") (pinfunction "K_2") (pintype "passive"))
      (node (ref "LED2") (pin "3") (pinfunction "K_3") (pintype "passive"))
      (node (ref "MSP1") (pin "33") (pinfunction "Thermal_pad_33") (pintype "power_in"))
      (node (ref "MSP1") (pin "5") (pinfunction "VSS_5") (pintype "power_in"))
      (node (ref "R11") (pin "1") (pinfunction "1_1") (pintype "passive"))
      (node (ref "R4") (pin "1") (pinfunction "1_1") (pintype "passive"))
      (node (ref "R6") (pin "2") (pinfunction "2_2") (pintype "passive"))
      (node (ref "R94") (pin "1") (pinfunction "1_1") (pintype "passive"))
      (node (ref "RT1") (pin "1") (pinfunction "1_1") (pintype "passive"))
      (node (ref "S1") (pin "1") (pinfunction "1_1") (pintype "passive"))
      (node (ref "S1") (pin "2") (pinfunction "2_2") (pintype "passive"))
      (node (ref "S2") (pin "1") (pinfunction "1_1") (pintype "passive"))
      (node (ref "S2") (pin "2") (pinfunction "2_2") (pintype "passive"))
      (node (ref "S2") (pin "4") (pinfunction "4_4") (pintype "passive"))
      (node (ref "S3") (pin "1") (pinfunction "1_1") (pintype "passive"))
      (node (ref "S3") (pin "2") (pinfunction "2_2") (pintype "passive"))
      (node (ref "S3") (pin "4") (pinfunction "4_4") (pintype "passive"))
    )
    (net (code "37") (name "Net-(C7-Pad2)") (class "Default")
      (node (ref "C7") (pin "2") (pinfunction "2_2") (pintype "passive"))
      (node (ref "J6") (pin "1") (pinfunction "1_1") (pintype "passive"))
      (node (ref "R5") (pin "2") (pinfunction "2_2") (pintype "passive"))
    )
    (net (code "38") (name "Net-(C9-Pad1)") (class "Default")
      (node (ref "C9") (pin "1") (pinfunction "1_1") (pintype "passive"))
      (node (ref "R16") (pin "2") (pinfunction "2_2") (pintype "passive"))
      (node (ref "R17") (pin "1") (pinfunction "1_1") (pintype "passive"))
    )
    (net (code "39") (name "Net-(C10-Pad1)") (class "Default")
      (node (ref "C10") (pin "1") (pinfunction "1_1") (pintype "passive"))
      (node (ref "R18") (pin "2") (pinfunction "2_2") (pintype "passive"))
      (node (ref "R19") (pin "1") (pinfunction "1_1") (pintype "passive"))
    )
    (net (code "40") (name "Net-(D1-CATHODE)") (class "Default")
      (node (ref "C7") (pin "1") (pinfunction "1_1") (pintype "passive"))
      (node (ref "D1") (pin "2") (pinfunction "CATHODE_2") (pintype "passive"))
      (node (ref "J5") (pin "1") (pinfunction "1_1") (pintype "passive"))
      (node (ref "R5") (pin "1") (pinfunction "1_1") (pintype "passive"))
    )
    (net (code "41") (name "Net-(J1-Pad2)") (class "Default")
      (node (ref "J1") (pin "2") (pinfunction "2_2") (pintype "passive"))
      (node (ref "R2") (pin "1") (pinfunction "1_1") (pintype "passive"))
      (node (ref "RT1") (pin "2") (pinfunction "2_2") (pintype "passive"))
    )
    (net (code "42") (name "Net-(J1-Pad3)") (class "Default")
      (node (ref "J1") (pin "3") (pinfunction "3_3") (pintype "passive"))
      (node (ref "R92") (pin "2") (pinfunction "2_2") (pintype "passive"))
    )
    (net (code "43") (name "Net-(J2-Pad1)") (class "Default")
      (node (ref "J2") (pin "1") (pinfunction "1_1") (pintype "passive"))
      (node (ref "R3") (pin "1") (pinfunction "1_1") (pintype "passive"))
    )
    (net (code "44") (name "Net-(J3-Pad1)") (class "Default")
      (node (ref "J3") (pin "1") (pinfunction "1_1") (pintype "passive"))
      (node (ref "R14") (pin "1") (pinfunction "1_1") (pintype "passive"))
    )
    (net (code "45") (name "Net-(J9-Pad1)") (class "Default")
      (node (ref "J9") (pin "1") (pinfunction "1_1") (pintype "passive"))
      (node (ref "R7") (pin "1") (pinfunction "1_1") (pintype "passive"))
    )
    (net (code "46") (name "Net-(J9-Pad3)") (class "Default")
      (node (ref "J9") (pin "3") (pinfunction "3_3") (pintype "passive"))
      (node (ref "R9") (pin "1") (pinfunction "1_1") (pintype "passive"))
    )
    (net (code "47") (name "Net-(J10-Pad1)") (class "Default")
      (node (ref "J10") (pin "1") (pinfunction "1_1") (pintype "passive"))
      (node (ref "R8") (pin "1") (pinfunction "1_1") (pintype "passive"))
    )
    (net (code "48") (name "Net-(J10-Pad3)") (class "Default")
      (node (ref "J10") (pin "3") (pinfunction "3_3") (pintype "passive"))
      (node (ref "R10") (pin "1") (pinfunction "1_1") (pintype "passive"))
    )
    (net (code "49") (name "Net-(J11-Pad1)") (class "Default")
      (node (ref "J11") (pin "1") (pinfunction "1_1") (pintype "passive"))
      (node (ref "R11") (pin "2") (pinfunction "2_2") (pintype "passive"))
      (node (ref "S1") (pin "4") (pinfunction "4_4") (pintype "passive"))
    )
    (net (code "50") (name "Net-(J12-Pad1)") (class "Default")
      (node (ref "J12") (pin "1") (pinfunction "1_1") (pintype "passive"))
      (node (ref "R13") (pin "2") (pinfunction "2_2") (pintype "passive"))
    )
    (net (code "51") (name "Net-(J13-Pad1)") (class "Default")
      (node (ref "J13") (pin "1") (pinfunction "1_1") (pintype "passive"))
      (node (ref "R15") (pin "2") (pinfunction "2_2") (pintype "passive"))
    )
    (net (code "52") (name "Net-(J14-Pad1)") (class "Default")
      (node (ref "J14") (pin "1") (pinfunction "1_1") (pintype "passive"))
      (node (ref "J2/J4") (pin "11") (pinfunction "GPIO_!_11") (pintype "passive"))
    )
    (net (code "53") (name "Net-(J14-Pad3)") (class "Default")
      (node (ref "J14") (pin "3") (pinfunction "3_3") (pintype "passive"))
      (node (ref "J2/J4") (pin "35") (pinfunction "Timer_Cap/GPIO_!_35") (pintype "passive"))
    )
    (net (code "54") (name "Net-(LED1-K)") (class "Default")
      (node (ref "LED1") (pin "2") (pinfunction "K_2") (pintype "passive"))
      (node (ref "R3") (pin "2") (pinfunction "2_2") (pintype "passive"))
    )
    (net (code "55") (name "Net-(LED2-A-Pad4)") (class "Default")
      (node (ref "LED2") (pin "4") (pinfunction "A_4") (pintype "passive"))
      (node (ref "R15") (pin "1") (pinfunction "1_1") (pintype "passive"))
    )
    (net (code "56") (name "Net-(LED2-A-Pad5)") (class "Default")
      (node (ref "LED2") (pin "5") (pinfunction "A_5") (pintype "passive"))
      (node (ref "R13") (pin "1") (pinfunction "1_1") (pintype "passive"))
    )
    (net (code "57") (name "Net-(LED2-A-Pad6)") (class "Default")
      (node (ref "LED2") (pin "6") (pinfunction "A_6") (pintype "passive"))
      (node (ref "R14") (pin "2") (pinfunction "2_2") (pintype "passive"))
    )
    (net (code "58") (name "Net-(MSP1-VCORE)") (class "Default")
      (node (ref "C12") (pin "1") (pinfunction "1_1") (pintype "passive"))
      (node (ref "C6") (pin "1") (pinfunction "1_1") (pintype "passive"))
      (node (ref "MSP1") (pin "32") (pinfunction "VCORE_32") (pintype "power_in"))
    )
    (net (code "59") (name "PA19_SWDIO") (class "Default")
      (node (ref "J2/J4") (pin "17") (pinfunction "GPIO_17") (pintype "passive"))
      (node (ref "MSP1") (pin "23") (pinfunction "PA19/SWDIO_23") (pintype "bidirectional"))
    )
    (net (code "60") (name "PA20_SWCLK") (class "Default")
      (node (ref "J2/J4") (pin "13") (pinfunction "SPI_CS/GPIO_!_13") (pintype "passive"))
      (node (ref "MSP1") (pin "24") (pinfunction "PA20/SWCLK/A6_24") (pintype "bidirectional"))
    )
    (net (code "61") (name "RST") (class "Default")
      (node (ref "C3") (pin "1") (pinfunction "1_1") (pintype "passive"))
      (node (ref "J2/J4") (pin "16") (pinfunction "RST_16") (pintype "passive"))
      (node (ref "MSP1") (pin "3") (pinfunction "~{RST}_3") (pintype "input"))
      (node (ref "R1") (pin "1") (pinfunction "1_1") (pintype "passive"))
      (node (ref "S3") (pin "3") (pinfunction "3_3") (pintype "passive"))
    )
    (net (code "62") (name "TARGET_RXD") (class "Default")
      (node (ref "J17") (pin "1") (pinfunction "1_1") (pintype "passive"))
    )
    (net (code "63") (name "TARGET_TXD") (class "Default")
      (node (ref "J16") (pin "1") (pinfunction "1_1") (pintype "passive"))
    )
    (net (code "64") (name "unconnected-(J1/J3-Analog_In{slash}I2S_SCLK-Pad28)") (class "Default")
      (node (ref "J1/J3") (pin "28") (pinfunction "Analog_In/I2S_SCLK_28") (pintype "passive"))
    )
    (net (code "65") (name "unconnected-(J1/J3-Analog_In{slash}I2S_WS-Pad27)") (class "Default")
      (node (ref "J1/J3") (pin "27") (pinfunction "Analog_In/I2S_WS_27") (pintype "passive"))
    )
    (net (code "66") (name "unconnected-(J1/J3-Analog_Out{slash}I2S_SDin-Pad30)") (class "Default")
      (node (ref "J1/J3") (pin "30") (pinfunction "Analog_Out/I2S_SDin_30") (pintype "passive"))
    )
    (net (code "67") (name "unconnected-(J1/J3-Analog_Out{slash}I2S_SDout-Pad29)") (class "Default")
      (node (ref "J1/J3") (pin "29") (pinfunction "Analog_Out/I2S_SDout_29") (pintype "passive"))
    )
    (net (code "68") (name "unconnected-(J2/J4-GPIO_!-Pad31)") (class "Default")
      (node (ref "J2/J4") (pin "31") (pinfunction "GPIO_!_31") (pintype "passive"))
    )
    (net (code "69") (name "unconnected-(J2/J4-GPIO_!-Pad32)") (class "Default")
      (node (ref "J2/J4") (pin "32") (pinfunction "GPIO_!_32") (pintype "passive"))
    )
    (net (code "70") (name "unconnected-(J2/J4-GPIO_!-Pad33)") (class "Default")
      (node (ref "J2/J4") (pin "33") (pinfunction "GPIO_!_33") (pintype "passive"))
    )
    (net (code "71") (name "unconnected-(J2/J4-GPIO_!-Pad34)") (class "Default")
      (node (ref "J2/J4") (pin "34") (pinfunction "GPIO_!_34") (pintype "passive"))
    )
  )
)
